# 07_power_input.net
KiCad netlist of a schematic drawn in Altium Designer
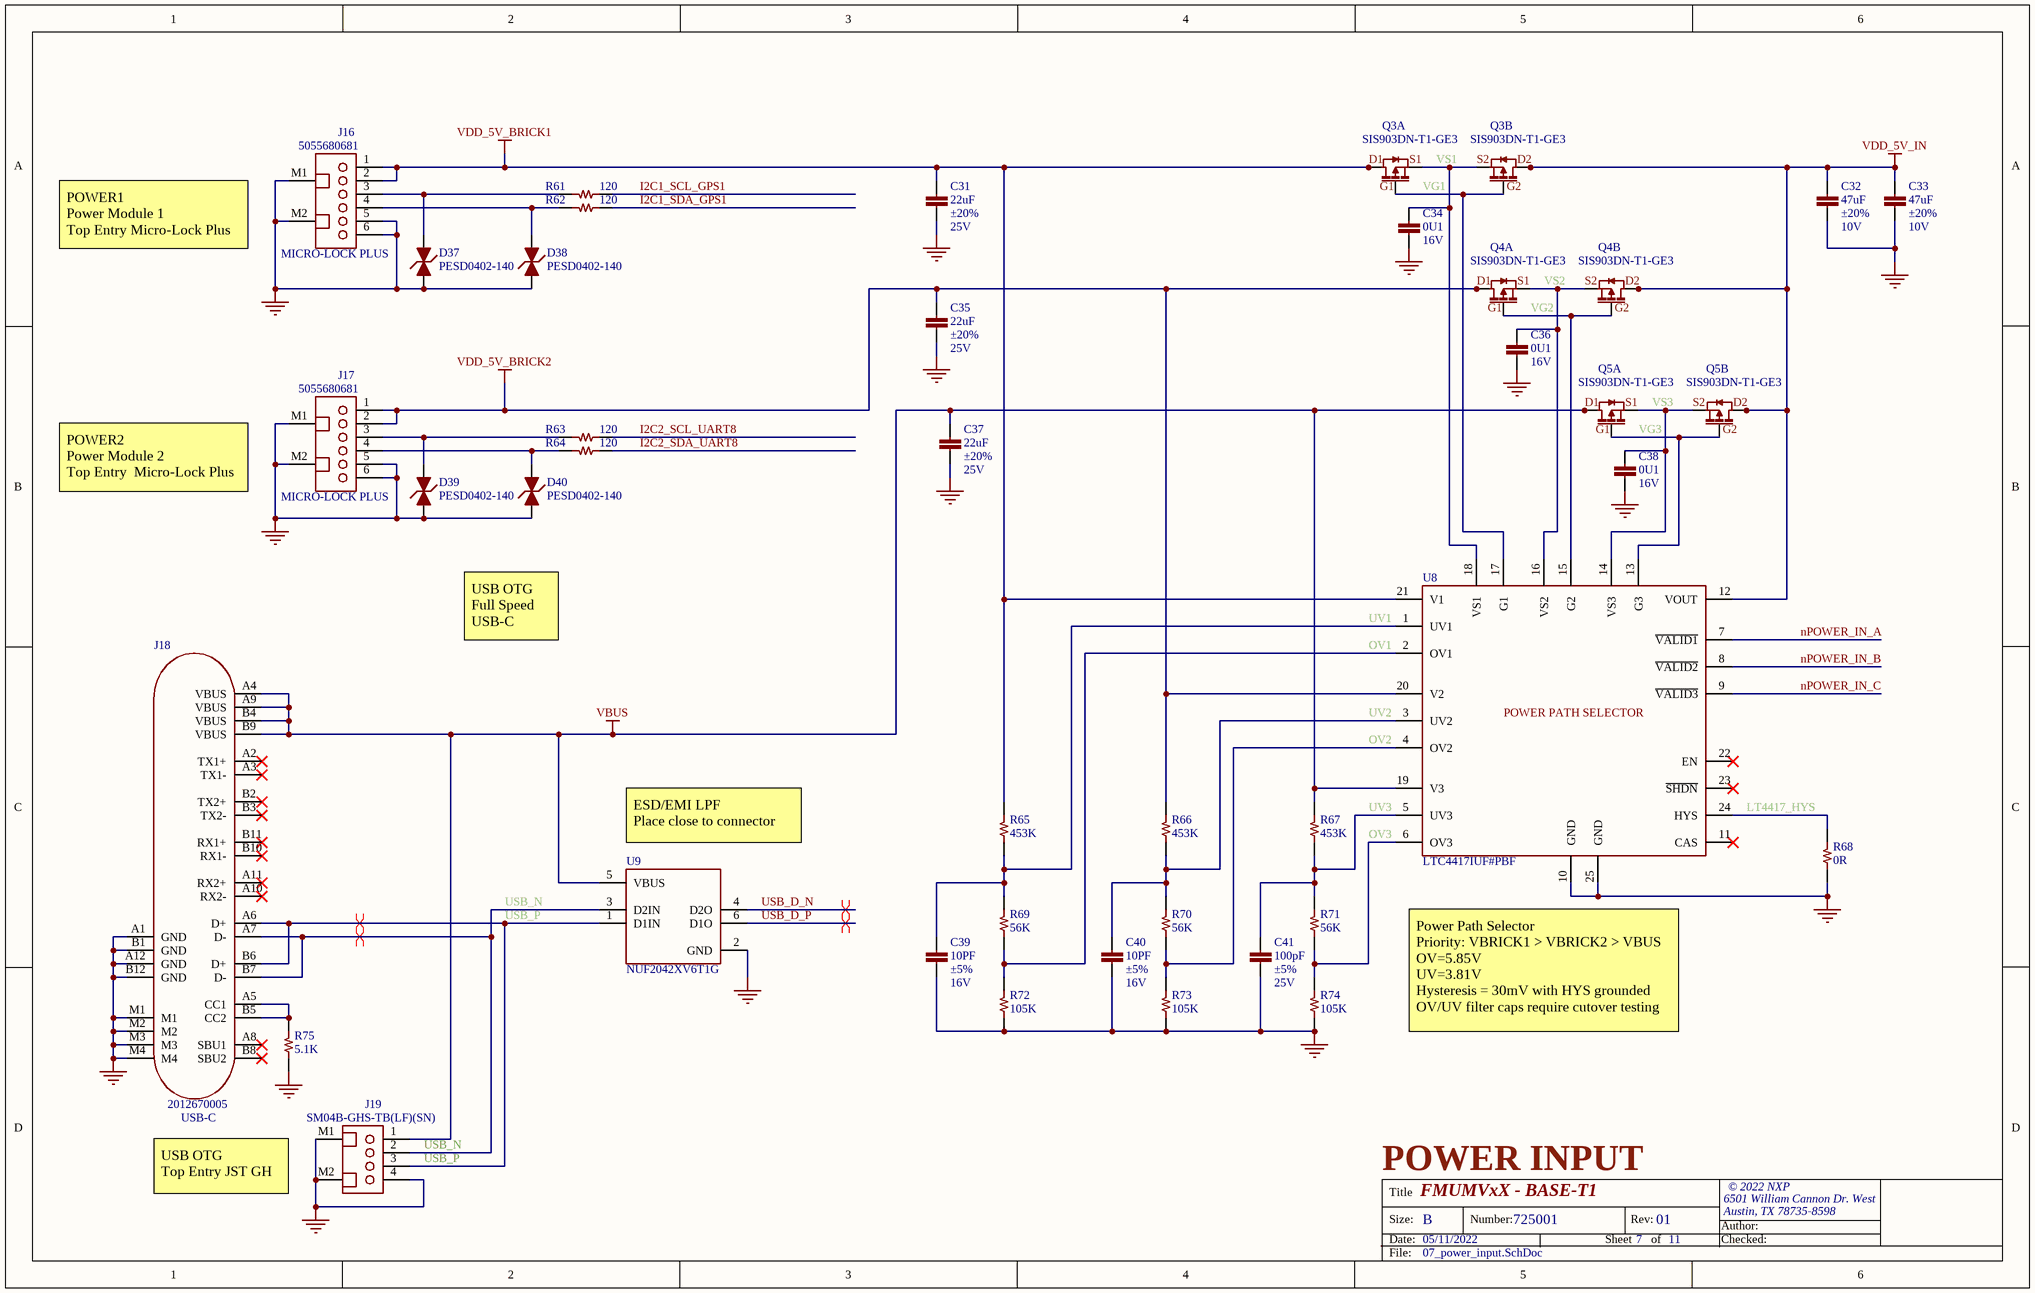
[diagram p0: 07_power_input.SchDoc]

(export (version "E")
  (design (tool "Eeschema 10.0.6"))
  (components
    (comp (ref "C31")
      (value "22uF")
      (footprint "CAPC200X125X70L40N")
      (description "CAP CER 22UF 20% 25V X5R 0805")
      (fields
        (field (name "MANUFACTURER") "Murata Electronics")
        (field (name "MANUFACTURER PART NUMBER") "GRT21BR61E226ME13L")
        (field (name "TOLERANCE") "±20%")
        (field (name "VOLTAGE - RATED") "25V")
      )
      (libsource (lib "NscDG_Integrated_Library") (part "CAP_22UF_20%_25V_X5R_0805"))
    )
    (comp (ref "C32")
      (value "47uF")
      (footprint "CAPC200X125X145L45N")
      (description "CAP CER 47UF 20% 10V X5R 0805")
      (fields
        (field (name "MANUFACTURER") "Murata Electronics North America")
        (field (name "MANUFACTURER PART NUMBER") "GRM21BR61A476ME15L")
        (field (name "TOLERANCE") "±20%")
        (field (name "VOLTAGE - RATED") "10V")
      )
      (libsource (lib "NscDG_Integrated_Library") (part "CAP_47UF_20%_10V_X5R_0805"))
    )
    (comp (ref "C33")
      (value "47uF")
      (footprint "CAPC200X125X145L45N")
      (description "CAP CER 47UF 20% 10V X5R 0805")
      (fields
        (field (name "MANUFACTURER") "Murata Electronics North America")
        (field (name "MANUFACTURER PART NUMBER") "GRM21BR61A476ME15L")
        (field (name "TOLERANCE") "±20%")
        (field (name "VOLTAGE - RATED") "10V")
      )
      (libsource (lib "NscDG_Integrated_Library") (part "CAP_47UF_20%_10V_X5R_0805"))
    )
    (comp (ref "C34")
      (value "0U1")
      (footprint "CAPC100X50X56L25N")
      (description "CAP CER 0.1UF 10% 16V X7R 0402")
      (fields
        (field (name "TOLERANCE") "±10%")
        (field (name "MANUFACTURER") "Murata Electronics")
        (field (name "VOLTAGE - RATED") "16V")
      )
      (libsource (lib "NscDG_Integrated_Library") (part "CAP_0U1_16V_X7R_0402"))
    )
    (comp (ref "C35")
      (value "22uF")
      (footprint "CAPC200X125X70L40N")
      (description "CAP CER 22UF 20% 25V X5R 0805")
      (fields
        (field (name "MANUFACTURER") "Murata Electronics")
        (field (name "MANUFACTURER PART NUMBER") "GRT21BR61E226ME13L")
        (field (name "TOLERANCE") "±20%")
        (field (name "VOLTAGE - RATED") "25V")
      )
      (libsource (lib "NscDG_Integrated_Library") (part "CAP_22UF_20%_25V_X5R_0805"))
    )
    (comp (ref "C36")
      (value "0U1")
      (footprint "CAPC100X50X56L25N")
      (description "CAP CER 0.1UF 10% 16V X7R 0402")
      (fields
        (field (name "TOLERANCE") "±10%")
        (field (name "MANUFACTURER") "Murata Electronics")
        (field (name "VOLTAGE - RATED") "16V")
      )
      (libsource (lib "NscDG_Integrated_Library") (part "CAP_0U1_16V_X7R_0402"))
    )
    (comp (ref "C37")
      (value "22uF")
      (footprint "CAPC200X125X70L40N")
      (description "CAP CER 22UF 20% 25V X5R 0805")
      (fields
        (field (name "MANUFACTURER") "Murata Electronics")
        (field (name "MANUFACTURER PART NUMBER") "GRT21BR61E226ME13L")
        (field (name "TOLERANCE") "±20%")
        (field (name "VOLTAGE - RATED") "25V")
      )
      (libsource (lib "NscDG_Integrated_Library") (part "CAP_22UF_20%_25V_X5R_0805"))
    )
    (comp (ref "C38")
      (value "0U1")
      (footprint "CAPC100X50X56L25N")
      (description "CAP CER 0.1UF 10% 16V X7R 0402")
      (fields
        (field (name "TOLERANCE") "±10%")
        (field (name "MANUFACTURER") "Murata Electronics")
        (field (name "VOLTAGE - RATED") "16V")
      )
      (libsource (lib "NscDG_Integrated_Library") (part "CAP_0U1_16V_X7R_0402"))
    )
    (comp (ref "C39")
      (value "10PF")
      (footprint "CAPC100X50X56L25N")
      (description "CAP CER 10PF 5% 16V C0G/NP0 0402")
      (fields
        (field (name "MANUFACTURER") "Wurth Electronics Inc.")
        (field (name "MANUFACTURER PART NUMBER") "885012005025")
        (field (name "TOLERANCE") "±5%")
        (field (name "VOLTAGE - RATED") "16V")
      )
      (libsource (lib "NscDG_Integrated_Library") (part "CAP_10PF_5%_16V_NPO_0402"))
    )
    (comp (ref "C40")
      (value "10PF")
      (footprint "CAPC100X50X56L25N")
      (description "CAP CER 10PF 5% 16V C0G/NP0 0402")
      (fields
        (field (name "MANUFACTURER") "Wurth Electronics Inc.")
        (field (name "MANUFACTURER PART NUMBER") "885012005025")
        (field (name "TOLERANCE") "±5%")
        (field (name "VOLTAGE - RATED") "16V")
      )
      (libsource (lib "NscDG_Integrated_Library") (part "CAP_10PF_5%_16V_NPO_0402"))
    )
    (comp (ref "C41")
      (value "100pF")
      (footprint "CAPC100X50X56L25N")
      (description "CAP CER 100PF 5% 25V COG/NPO 0402")
      (fields
        (field (name "MANUFACTURER") "KEMET")
        (field (name "MANUFACTURER PART NUMBER") "C0402C101J3GACTU")
        (field (name "TOLERANCE") "±5%")
        (field (name "VOLTAGE - RATED") "25V")
      )
      (libsource (lib "NscDG_Integrated_Library") (part "CAP_100PF_5%_25V_NPO_0402"))
    )
    (comp (ref "D37")
      (value "DIODE TVS BIDIRECTIONAL 14VWM 40VC 0402")
      (footprint "DIONC100X50X43L20N")
      (fields
        (field (name "MANUFACTURER") "Littelfuse Inc.")
        (field (name "MANUFACTURER PART NUMBER") "PESD0402-140")
      )
      (libsource (lib "NscDG_Integrated_Library") (part "DIODE_TVS_0402"))
    )
    (comp (ref "D38")
      (value "DIODE TVS BIDIRECTIONAL 14VWM 40VC 0402")
      (footprint "DIONC100X50X43L20N")
      (fields
        (field (name "MANUFACTURER") "Littelfuse Inc.")
        (field (name "MANUFACTURER PART NUMBER") "PESD0402-140")
      )
      (libsource (lib "NscDG_Integrated_Library") (part "DIODE_TVS_0402"))
    )
    (comp (ref "D39")
      (value "DIODE TVS BIDIRECTIONAL 14VWM 40VC 0402")
      (footprint "DIONC100X50X43L20N")
      (fields
        (field (name "MANUFACTURER") "Littelfuse Inc.")
        (field (name "MANUFACTURER PART NUMBER") "PESD0402-140")
      )
      (libsource (lib "NscDG_Integrated_Library") (part "DIODE_TVS_0402"))
    )
    (comp (ref "D40")
      (value "DIODE TVS BIDIRECTIONAL 14VWM 40VC 0402")
      (footprint "DIONC100X50X43L20N")
      (fields
        (field (name "MANUFACTURER") "Littelfuse Inc.")
        (field (name "MANUFACTURER PART NUMBER") "PESD0402-140")
      )
      (libsource (lib "NscDG_Integrated_Library") (part "DIODE_TVS_0402"))
    )
    (comp (ref "J16")
      (value "CONN HEADER MICRO-LOCK PLUS TOP 6POS 1.25MM SMT")
      (footprint "MOLEX_505568-0681")
      (fields
        (field (name "MANUFACTURER") "Molex, LLC")
        (field (name "ID") "MICRO-LOCK PLUS")
        (field (name "MANUFACTURER PART NUMBER") "5055680681")
      )
      (libsource (lib "NscDG_Integrated_Library") (part "CONN_HDR_1X6_RCPT_1.25MM_VERT_SMT"))
    )
    (comp (ref "J17")
      (value "CONN HEADER MICRO-LOCK PLUS TOP 6POS 1.25MM SMT")
      (footprint "MOLEX_505568-0681")
      (fields
        (field (name "MANUFACTURER") "Molex, LLC")
        (field (name "ID") "MICRO-LOCK PLUS")
        (field (name "MANUFACTURER PART NUMBER") "5055680681")
      )
      (libsource (lib "NscDG_Integrated_Library") (part "CONN_HDR_1X6_RCPT_1.25MM_VERT_SMT"))
    )
    (comp (ref "J18")
      (value "CONN RCPT USB C 3.1 SMT R/A SMD")
      (footprint "MOLEX_2012670005")
      (fields
        (field (name "MANUFACTURER") "Molex, LLC")
        (field (name "ID") "USB-C")
        (field (name "MANUFACTURER PART NUMBER") "2012670005")
      )
      (libsource (lib "NscDG_Integrated_Library") (part "CONN_RCPT_24POS_USB-C_RA-3_SMD"))
    )
    (comp (ref "J19")
      (value "CONN HEADER GH SIDE 4POS 1.25MM SMT")
      (footprint "JST_SM04B-GHS-TBLFSN")
      (fields
        (field (name "MANUFACTURER") "JST Sales America Inc.")
        (field (name "MANUFACTURER PART NUMBER") "SM04B-GHS-TB(LF)(SN)")
      )
      (libsource (lib "NscDG_Integrated_Library") (part "CONN_JST_GH_4PIN_RA_SMT"))
    )
    (comp (ref "Q3")
      (value "TRAN MOSFET 2P-CH 20V 6A PowerPAK")
      (footprint "VISHAY_POWERPAK_1212-8_DUAL")
      (fields
        (field (name "MANUFACTURER") "Vishay Siliconix")
        (field (name "MANUFACTURER PART NUMBER") "SIS903DN-T1-GE3")
      )
      (libsource (lib "NscDG_Integrated_Library") (part "TRAN_MOSFET_DUAL_PCHANNEL_PowerPAK"))
    )
    (comp (ref "Q4")
      (value "TRAN MOSFET 2P-CH 20V 6A PowerPAK")
      (footprint "VISHAY_POWERPAK_1212-8_DUAL")
      (fields
        (field (name "MANUFACTURER") "Vishay Siliconix")
        (field (name "MANUFACTURER PART NUMBER") "SIS903DN-T1-GE3")
      )
      (libsource (lib "NscDG_Integrated_Library") (part "TRAN_MOSFET_DUAL_PCHANNEL_PowerPAK"))
    )
    (comp (ref "Q5")
      (value "TRAN MOSFET 2P-CH 20V 6A PowerPAK")
      (footprint "VISHAY_POWERPAK_1212-8_DUAL")
      (fields
        (field (name "MANUFACTURER") "Vishay Siliconix")
        (field (name "MANUFACTURER PART NUMBER") "SIS903DN-T1-GE3")
      )
      (libsource (lib "NscDG_Integrated_Library") (part "TRAN_MOSFET_DUAL_PCHANNEL_PowerPAK"))
    )
    (comp (ref "R61")
      (value "120")
      (footprint "RESC100X50X40L25")
      (description "RES SMD 120 OHM 1% 1/16W 0402")
      (fields (field (name "TOLERANCE") "±1%") (field (name "MANUFACTURER") "Yageo"))
      (libsource (lib "NscDG_Integrated_Library") (part "RES_120_1%_1/16W_0402"))
    )
    (comp (ref "R62")
      (value "120")
      (footprint "RESC100X50X40L25")
      (description "RES SMD 120 OHM 1% 1/16W 0402")
      (fields (field (name "TOLERANCE") "±1%") (field (name "MANUFACTURER") "Yageo"))
      (libsource (lib "NscDG_Integrated_Library") (part "RES_120_1%_1/16W_0402"))
    )
    (comp (ref "R63")
      (value "120")
      (footprint "RESC100X50X40L25")
      (description "RES SMD 120 OHM 1% 1/16W 0402")
      (fields (field (name "TOLERANCE") "±1%") (field (name "MANUFACTURER") "Yageo"))
      (libsource (lib "NscDG_Integrated_Library") (part "RES_120_1%_1/16W_0402"))
    )
    (comp (ref "R64")
      (value "120")
      (footprint "RESC100X50X40L25")
      (description "RES SMD 120 OHM 1% 1/16W 0402")
      (fields (field (name "TOLERANCE") "±1%") (field (name "MANUFACTURER") "Yageo"))
      (libsource (lib "NscDG_Integrated_Library") (part "RES_120_1%_1/16W_0402"))
    )
    (comp (ref "R65")
      (value "453K")
      (footprint "RESC100X50X40L25")
      (description "RES SMD 453K OHM 1% 1/16W 0402")
      (fields (field (name "TOLERANCE") "±1%") (field (name "MANUFACTURER") "Yageo"))
      (libsource (lib "NscDG_Integrated_Library") (part "RES_453K_1%_1/16W_0402"))
    )
    (comp (ref "R66")
      (value "453K")
      (footprint "RESC100X50X40L25")
      (description "RES SMD 453K OHM 1% 1/16W 0402")
      (fields (field (name "TOLERANCE") "±1%") (field (name "MANUFACTURER") "Yageo"))
      (libsource (lib "NscDG_Integrated_Library") (part "RES_453K_1%_1/16W_0402"))
    )
    (comp (ref "R67")
      (value "453K")
      (footprint "RESC100X50X40L25")
      (description "RES SMD 453K OHM 1% 1/16W 0402")
      (fields (field (name "TOLERANCE") "±1%") (field (name "MANUFACTURER") "Yageo"))
      (libsource (lib "NscDG_Integrated_Library") (part "RES_453K_1%_1/16W_0402"))
    )
    (comp (ref "R68")
      (value "0R")
      (footprint "RESC100X50X40L25")
      (description "RES SMD 0 OHM 1% 1/16W 0402")
      (fields (field (name "TOLERANCE") "±1%") (field (name "MANUFACTURER") "Yageo"))
      (libsource (lib "NscDG_Integrated_Library") (part "RES_0R_1%_1/16W_0402"))
    )
    (comp (ref "R69")
      (value "56K")
      (footprint "RESC100X50X40L25")
      (description "RES SMD 56K OHM 1% 1/16W 0402")
      (fields (field (name "TOLERANCE") "±1%") (field (name "MANUFACTURER") "Yageo"))
      (libsource (lib "NscDG_Integrated_Library") (part "RES_56K_1%_1/16W_0402"))
    )
    (comp (ref "R70")
      (value "56K")
      (footprint "RESC100X50X40L25")
      (description "RES SMD 56K OHM 1% 1/16W 0402")
      (fields (field (name "TOLERANCE") "±1%") (field (name "MANUFACTURER") "Yageo"))
      (libsource (lib "NscDG_Integrated_Library") (part "RES_56K_1%_1/16W_0402"))
    )
    (comp (ref "R71")
      (value "56K")
      (footprint "RESC100X50X40L25")
      (description "RES SMD 56K OHM 1% 1/16W 0402")
      (fields (field (name "TOLERANCE") "±1%") (field (name "MANUFACTURER") "Yageo"))
      (libsource (lib "NscDG_Integrated_Library") (part "RES_56K_1%_1/16W_0402"))
    )
    (comp (ref "R72")
      (value "105K")
      (footprint "RESC100X50X40L25")
      (description "RES SMD 105K OHM 1% 1/16W 0402")
      (fields (field (name "TOLERANCE") "±1%") (field (name "MANUFACTURER") "Yageo"))
      (libsource (lib "NscDG_Integrated_Library") (part "RES_105K_1%_1/16W_0402"))
    )
    (comp (ref "R73")
      (value "105K")
      (footprint "RESC100X50X40L25")
      (description "RES SMD 105K OHM 1% 1/16W 0402")
      (fields (field (name "TOLERANCE") "±1%") (field (name "MANUFACTURER") "Yageo"))
      (libsource (lib "NscDG_Integrated_Library") (part "RES_105K_1%_1/16W_0402"))
    )
    (comp (ref "R74")
      (value "105K")
      (footprint "RESC100X50X40L25")
      (description "RES SMD 105K OHM 1% 1/16W 0402")
      (fields (field (name "TOLERANCE") "±1%") (field (name "MANUFACTURER") "Yageo"))
      (libsource (lib "NscDG_Integrated_Library") (part "RES_105K_1%_1/16W_0402"))
    )
    (comp (ref "R75")
      (value "5.1K")
      (footprint "RESC100X50X40L25")
      (description "RES SMD 5.1K OHM 1% 1/16W 0402")
      (fields (field (name "TOLERANCE") "±1%") (field (name "MANUFACTURER") "Yageo"))
      (libsource (lib "NscDG_Integrated_Library") (part "RES_5.1K_1%_1/16W_0402"))
    )
    (comp (ref "U8")
      (value "IC OR CTRLR SRC SELECT 24QFN")
      (footprint "QFN25P50_400X400X80L40X25T245N")
      (fields
        (field (name "MANUFACTURER") "Linear Technology/Analog Devices")
        (field (name "MANUFACTURER PART NUMBER") "LTC4417IUF#PBF")
      )
      (libsource (lib "NscDG_Integrated_Library") (part "IC_LTC4417"))
    )
    (comp (ref "U9")
      (value "IC FILTER RC(PI) 22 OHM/42PF SOT-563")
      (footprint "SOFL6P50_160X160X60L20X22")
      (fields
        (field (name "MANUFACTURER") "ON Semiconductor")
        (field (name "MANUFACTURER PART NUMBER") "NUF2042XV6T1G")
      )
      (libsource (lib "NscDG_Integrated_Library") (part "IC_NUF2042XV6_SOT563"))
    )
  )
  (nets
    (net (code "1") (name "/I2C1_SCL_GPS1") (class "Default")
      (node (ref "R61") (pin "2") (pinfunction "2_2") (pintype "passive"))
    )
    (net (code "2") (name "/I2C1_SDA_GPS1") (class "Default")
      (node (ref "R62") (pin "2") (pinfunction "2_2") (pintype "passive"))
    )
    (net (code "3") (name "/I2C2_SCL_UART8") (class "Default")
      (node (ref "R63") (pin "2") (pinfunction "2_2") (pintype "passive"))
    )
    (net (code "4") (name "/I2C2_SDA_UART8") (class "Default")
      (node (ref "R64") (pin "2") (pinfunction "2_2") (pintype "passive"))
    )
    (net (code "5") (name "/LT4417_HYS") (class "Default")
      (node (ref "R68") (pin "1") (pinfunction "1_1") (pintype "passive"))
      (node (ref "U8") (pin "24") (pinfunction "HYS_24") (pintype "passive"))
    )
    (net (code "6") (name "/OV1") (class "Default")
      (node (ref "R69") (pin "2") (pinfunction "2_2") (pintype "passive"))
      (node (ref "R72") (pin "1") (pinfunction "1_1") (pintype "passive"))
      (node (ref "U8") (pin "2") (pinfunction "OV1_2") (pintype "passive"))
    )
    (net (code "7") (name "/OV2") (class "Default")
      (node (ref "R70") (pin "2") (pinfunction "2_2") (pintype "passive"))
      (node (ref "R73") (pin "1") (pinfunction "1_1") (pintype "passive"))
      (node (ref "U8") (pin "4") (pinfunction "OV2_4") (pintype "passive"))
    )
    (net (code "8") (name "/OV3") (class "Default")
      (node (ref "R71") (pin "2") (pinfunction "2_2") (pintype "passive"))
      (node (ref "R74") (pin "1") (pinfunction "1_1") (pintype "passive"))
      (node (ref "U8") (pin "6") (pinfunction "OV3_6") (pintype "passive"))
    )
    (net (code "9") (name "/USB_D_N") (class "Default")
      (node (ref "U9") (pin "4") (pinfunction "D2O_4") (pintype "passive"))
    )
    (net (code "10") (name "/USB_D_P") (class "Default")
      (node (ref "U9") (pin "6") (pinfunction "D1O_6") (pintype "passive"))
    )
    (net (code "11") (name "/USB_N") (class "Default")
      (node (ref "J18") (pin "A7") (pinfunction "D-_A7") (pintype "passive"))
      (node (ref "J18") (pin "B7") (pinfunction "D-_B7") (pintype "passive"))
      (node (ref "J19") (pin "2") (pinfunction "2_2") (pintype "passive"))
      (node (ref "U9") (pin "3") (pinfunction "D2IN_3") (pintype "passive"))
    )
    (net (code "12") (name "/USB_P") (class "Default")
      (node (ref "J18") (pin "A6") (pinfunction "D+_A6") (pintype "passive"))
      (node (ref "J18") (pin "B6") (pinfunction "D+_B6") (pintype "passive"))
      (node (ref "J19") (pin "3") (pinfunction "3_3") (pintype "passive"))
      (node (ref "U9") (pin "1") (pinfunction "D1IN_1") (pintype "passive"))
    )
    (net (code "13") (name "/UV1") (class "Default")
      (node (ref "C39") (pin "1") (pinfunction "1_1") (pintype "passive"))
      (node (ref "R65") (pin "2") (pinfunction "2_2") (pintype "passive"))
      (node (ref "R69") (pin "1") (pinfunction "1_1") (pintype "passive"))
      (node (ref "U8") (pin "1") (pinfunction "UV1_1") (pintype "passive"))
    )
    (net (code "14") (name "/UV2") (class "Default")
      (node (ref "C40") (pin "1") (pinfunction "1_1") (pintype "passive"))
      (node (ref "R66") (pin "2") (pinfunction "2_2") (pintype "passive"))
      (node (ref "R70") (pin "1") (pinfunction "1_1") (pintype "passive"))
      (node (ref "U8") (pin "3") (pinfunction "UV2_3") (pintype "passive"))
    )
    (net (code "15") (name "/UV3") (class "Default")
      (node (ref "C41") (pin "1") (pinfunction "1_1") (pintype "passive"))
      (node (ref "R67") (pin "2") (pinfunction "2_2") (pintype "passive"))
      (node (ref "R71") (pin "1") (pinfunction "1_1") (pintype "passive"))
      (node (ref "U8") (pin "5") (pinfunction "UV3_5") (pintype "passive"))
    )
    (net (code "16") (name "/VG1") (class "Default")
      (node (ref "Q3") (pin "2") (pinfunction "G1_2") (pintype "passive"))
      (node (ref "Q3") (pin "4") (pinfunction "G2_4") (pintype "passive"))
      (node (ref "U8") (pin "17") (pinfunction "G1_17") (pintype "passive"))
    )
    (net (code "17") (name "/VG2") (class "Default")
      (node (ref "Q4") (pin "2") (pinfunction "G1_2") (pintype "passive"))
      (node (ref "Q4") (pin "4") (pinfunction "G2_4") (pintype "passive"))
      (node (ref "U8") (pin "15") (pinfunction "G2_15") (pintype "passive"))
    )
    (net (code "18") (name "/VG3") (class "Default")
      (node (ref "Q5") (pin "2") (pinfunction "G1_2") (pintype "passive"))
      (node (ref "Q5") (pin "4") (pinfunction "G2_4") (pintype "passive"))
      (node (ref "U8") (pin "13") (pinfunction "G3_13") (pintype "passive"))
    )
    (net (code "19") (name "/VS1") (class "Default")
      (node (ref "C34") (pin "1") (pinfunction "1_1") (pintype "passive"))
      (node (ref "Q3") (pin "1") (pinfunction "S1_1") (pintype "passive"))
      (node (ref "Q3") (pin "3") (pinfunction "S2_3") (pintype "passive"))
      (node (ref "U8") (pin "18") (pinfunction "VS1_18") (pintype "passive"))
    )
    (net (code "20") (name "/VS2") (class "Default")
      (node (ref "C36") (pin "1") (pinfunction "1_1") (pintype "passive"))
      (node (ref "Q4") (pin "1") (pinfunction "S1_1") (pintype "passive"))
      (node (ref "Q4") (pin "3") (pinfunction "S2_3") (pintype "passive"))
      (node (ref "U8") (pin "16") (pinfunction "VS2_16") (pintype "passive"))
    )
    (net (code "21") (name "/VS3") (class "Default")
      (node (ref "C38") (pin "1") (pinfunction "1_1") (pintype "passive"))
      (node (ref "Q5") (pin "1") (pinfunction "S1_1") (pintype "passive"))
      (node (ref "Q5") (pin "3") (pinfunction "S2_3") (pintype "passive"))
      (node (ref "U8") (pin "14") (pinfunction "VS3_14") (pintype "passive"))
    )
    (net (code "22") (name "/nPOWER_IN_A") (class "Default")
      (node (ref "U8") (pin "7") (pinfunction "~{VALID1}_7") (pintype "passive"))
    )
    (net (code "23") (name "/nPOWER_IN_B") (class "Default")
      (node (ref "U8") (pin "8") (pinfunction "~{VALID2}_8") (pintype "passive"))
    )
    (net (code "24") (name "/nPOWER_IN_C") (class "Default")
      (node (ref "U8") (pin "9") (pinfunction "~{VALID3}_9") (pintype "passive"))
    )
    (net (code "25") (name "GND") (class "Default")
      (node (ref "C31") (pin "2") (pinfunction "2_2") (pintype "passive"))
      (node (ref "C32") (pin "2") (pinfunction "2_2") (pintype "passive"))
      (node (ref "C33") (pin "2") (pinfunction "2_2") (pintype "passive"))
      (node (ref "C34") (pin "2") (pinfunction "2_2") (pintype "passive"))
      (node (ref "C35") (pin "2") (pinfunction "2_2") (pintype "passive"))
      (node (ref "C36") (pin "2") (pinfunction "2_2") (pintype "passive"))
      (node (ref "C37") (pin "2") (pinfunction "2_2") (pintype "passive"))
      (node (ref "C38") (pin "2") (pinfunction "2_2") (pintype "passive"))
      (node (ref "C39") (pin "2") (pinfunction "2_2") (pintype "passive"))
      (node (ref "C40") (pin "2") (pinfunction "2_2") (pintype "passive"))
      (node (ref "C41") (pin "2") (pinfunction "2_2") (pintype "passive"))
      (node (ref "D37") (pin "1") (pinfunction "1_1") (pintype "passive"))
      (node (ref "D38") (pin "1") (pinfunction "1_1") (pintype "passive"))
      (node (ref "D39") (pin "1") (pinfunction "1_1") (pintype "passive"))
      (node (ref "D40") (pin "1") (pinfunction "1_1") (pintype "passive"))
      (node (ref "J16") (pin "5") (pinfunction "5_5") (pintype "passive"))
      (node (ref "J16") (pin "6") (pinfunction "6_6") (pintype "passive"))
      (node (ref "J16") (pin "M1") (pinfunction "M1_M1") (pintype "passive"))
      (node (ref "J16") (pin "M2") (pinfunction "M2_M2") (pintype "passive"))
      (node (ref "J17") (pin "5") (pinfunction "5_5") (pintype "passive"))
      (node (ref "J17") (pin "6") (pinfunction "6_6") (pintype "passive"))
      (node (ref "J17") (pin "M1") (pinfunction "M1_M1") (pintype "passive"))
      (node (ref "J17") (pin "M2") (pinfunction "M2_M2") (pintype "passive"))
      (node (ref "J18") (pin "A1") (pinfunction "GND_A1") (pintype "passive"))
      (node (ref "J18") (pin "A12") (pinfunction "GND_A12") (pintype "passive"))
      (node (ref "J18") (pin "B1") (pinfunction "GND_B1") (pintype "passive"))
      (node (ref "J18") (pin "B12") (pinfunction "GND_B12") (pintype "passive"))
      (node (ref "J18") (pin "M1") (pinfunction "M1_M1") (pintype "passive"))
      (node (ref "J18") (pin "M2") (pinfunction "M2_M2") (pintype "passive"))
      (node (ref "J18") (pin "M3") (pinfunction "M3_M3") (pintype "passive"))
      (node (ref "J18") (pin "M4") (pinfunction "M4_M4") (pintype "passive"))
      (node (ref "J19") (pin "4") (pinfunction "4_4") (pintype "passive"))
      (node (ref "J19") (pin "M1") (pinfunction "M1_M1") (pintype "passive"))
      (node (ref "J19") (pin "M2") (pinfunction "M2_M2") (pintype "passive"))
      (node (ref "R68") (pin "2") (pinfunction "2_2") (pintype "passive"))
      (node (ref "R72") (pin "2") (pinfunction "2_2") (pintype "passive"))
      (node (ref "R73") (pin "2") (pinfunction "2_2") (pintype "passive"))
      (node (ref "R74") (pin "2") (pinfunction "2_2") (pintype "passive"))
      (node (ref "R75") (pin "2") (pinfunction "2_2") (pintype "passive"))
      (node (ref "U8") (pin "10") (pinfunction "GND_10") (pintype "passive"))
      (node (ref "U8") (pin "25") (pinfunction "GND_25") (pintype "passive"))
      (node (ref "U9") (pin "2") (pinfunction "GND_2") (pintype "passive"))
    )
    (net (code "26") (name "Net-(D37-Pad2)") (class "Default")
      (node (ref "D37") (pin "2") (pinfunction "2_2") (pintype "passive"))
      (node (ref "J16") (pin "3") (pinfunction "3_3") (pintype "passive"))
      (node (ref "R61") (pin "1") (pinfunction "1_1") (pintype "passive"))
    )
    (net (code "27") (name "Net-(D38-Pad2)") (class "Default")
      (node (ref "D38") (pin "2") (pinfunction "2_2") (pintype "passive"))
      (node (ref "J16") (pin "4") (pinfunction "4_4") (pintype "passive"))
      (node (ref "R62") (pin "1") (pinfunction "1_1") (pintype "passive"))
    )
    (net (code "28") (name "Net-(D39-Pad2)") (class "Default")
      (node (ref "D39") (pin "2") (pinfunction "2_2") (pintype "passive"))
      (node (ref "J17") (pin "3") (pinfunction "3_3") (pintype "passive"))
      (node (ref "R63") (pin "1") (pinfunction "1_1") (pintype "passive"))
    )
    (net (code "29") (name "Net-(D40-Pad2)") (class "Default")
      (node (ref "D40") (pin "2") (pinfunction "2_2") (pintype "passive"))
      (node (ref "J17") (pin "4") (pinfunction "4_4") (pintype "passive"))
      (node (ref "R64") (pin "1") (pinfunction "1_1") (pintype "passive"))
    )
    (net (code "30") (name "Net-(J18-CC1)") (class "Default")
      (node (ref "J18") (pin "A5") (pinfunction "CC1_A5") (pintype "passive"))
      (node (ref "J18") (pin "B5") (pinfunction "CC2_B5") (pintype "passive"))
      (node (ref "R75") (pin "1") (pinfunction "1_1") (pintype "passive"))
    )
    (net (code "31") (name "VBUS") (class "Default")
      (node (ref "C37") (pin "1") (pinfunction "1_1") (pintype "passive"))
      (node (ref "J18") (pin "A4") (pinfunction "VBUS_A4") (pintype "power_in"))
      (node (ref "J18") (pin "A9") (pinfunction "VBUS_A9") (pintype "power_in"))
      (node (ref "J18") (pin "B4") (pinfunction "VBUS_B4") (pintype "power_in"))
      (node (ref "J18") (pin "B9") (pinfunction "VBUS_B9") (pintype "power_in"))
      (node (ref "J19") (pin "1") (pinfunction "1_1") (pintype "passive"))
      (node (ref "Q5") (pin "7") (pinfunction "D1_7") (pintype "passive"))
      (node (ref "Q5") (pin "8") (pinfunction "D1_8") (pintype "passive"))
      (node (ref "R67") (pin "1") (pinfunction "1_1") (pintype "passive"))
      (node (ref "U8") (pin "19") (pinfunction "V3_19") (pintype "passive"))
      (node (ref "U9") (pin "5") (pinfunction "VBUS_5") (pintype "power_in"))
    )
    (net (code "32") (name "VDD_5V_BRICK1") (class "Default")
      (node (ref "C31") (pin "1") (pinfunction "1_1") (pintype "passive"))
      (node (ref "J16") (pin "1") (pinfunction "1_1") (pintype "passive"))
      (node (ref "J16") (pin "2") (pinfunction "2_2") (pintype "passive"))
      (node (ref "Q3") (pin "7") (pinfunction "D1_7") (pintype "passive"))
      (node (ref "Q3") (pin "8") (pinfunction "D1_8") (pintype "passive"))
      (node (ref "R65") (pin "1") (pinfunction "1_1") (pintype "passive"))
      (node (ref "U8") (pin "21") (pinfunction "V1_21") (pintype "passive"))
    )
    (net (code "33") (name "VDD_5V_BRICK2") (class "Default")
      (node (ref "C35") (pin "1") (pinfunction "1_1") (pintype "passive"))
      (node (ref "J17") (pin "1") (pinfunction "1_1") (pintype "passive"))
      (node (ref "J17") (pin "2") (pinfunction "2_2") (pintype "passive"))
      (node (ref "Q4") (pin "7") (pinfunction "D1_7") (pintype "passive"))
      (node (ref "Q4") (pin "8") (pinfunction "D1_8") (pintype "passive"))
      (node (ref "R66") (pin "1") (pinfunction "1_1") (pintype "passive"))
      (node (ref "U8") (pin "20") (pinfunction "V2_20") (pintype "passive"))
    )
    (net (code "34") (name "VDD_5V_IN") (class "Default")
      (node (ref "C32") (pin "1") (pinfunction "1_1") (pintype "passive"))
      (node (ref "C33") (pin "1") (pinfunction "1_1") (pintype "passive"))
      (node (ref "Q3") (pin "5") (pinfunction "D2_5") (pintype "passive"))
      (node (ref "Q3") (pin "6") (pinfunction "D2_6") (pintype "passive"))
      (node (ref "Q4") (pin "5") (pinfunction "D2_5") (pintype "passive"))
      (node (ref "Q4") (pin "6") (pinfunction "D2_6") (pintype "passive"))
      (node (ref "Q5") (pin "5") (pinfunction "D2_5") (pintype "passive"))
      (node (ref "Q5") (pin "6") (pinfunction "D2_6") (pintype "passive"))
      (node (ref "U8") (pin "12") (pinfunction "VOUT_12") (pintype "passive"))
    )
    (net (code "35") (name "unconnected-(J18-RX1+-PadB11)") (class "Default")
      (node (ref "J18") (pin "B11") (pinfunction "RX1+_B11") (pintype "passive+no_connect"))
    )
    (net (code "36") (name "unconnected-(J18-RX1--PadB10)") (class "Default")
      (node (ref "J18") (pin "B10") (pinfunction "RX1-_B10") (pintype "passive+no_connect"))
    )
    (net (code "37") (name "unconnected-(J18-RX2+-PadA11)") (class "Default")
      (node (ref "J18") (pin "A11") (pinfunction "RX2+_A11") (pintype "passive+no_connect"))
    )
    (net (code "38") (name "unconnected-(J18-RX2--PadA10)") (class "Default")
      (node (ref "J18") (pin "A10") (pinfunction "RX2-_A10") (pintype "passive+no_connect"))
    )
    (net (code "39") (name "unconnected-(J18-SBU1-PadA8)") (class "Default")
      (node (ref "J18") (pin "A8") (pinfunction "SBU1_A8") (pintype "passive+no_connect"))
    )
    (net (code "40") (name "unconnected-(J18-SBU2-PadB8)") (class "Default")
      (node (ref "J18") (pin "B8") (pinfunction "SBU2_B8") (pintype "passive+no_connect"))
    )
    (net (code "41") (name "unconnected-(J18-TX1+-PadA2)") (class "Default")
      (node (ref "J18") (pin "A2") (pinfunction "TX1+_A2") (pintype "passive+no_connect"))
    )
    (net (code "42") (name "unconnected-(J18-TX1--PadA3)") (class "Default")
      (node (ref "J18") (pin "A3") (pinfunction "TX1-_A3") (pintype "passive+no_connect"))
    )
    (net (code "43") (name "unconnected-(J18-TX2+-PadB2)") (class "Default")
      (node (ref "J18") (pin "B2") (pinfunction "TX2+_B2") (pintype "passive+no_connect"))
    )
    (net (code "44") (name "unconnected-(J18-TX2--PadB3)") (class "Default")
      (node (ref "J18") (pin "B3") (pinfunction "TX2-_B3") (pintype "passive+no_connect"))
    )
    (net (code "45") (name "unconnected-(U8-CAS-Pad11)") (class "Default")
      (node (ref "U8") (pin "11") (pinfunction "CAS_11") (pintype "passive+no_connect"))
    )
    (net (code "46") (name "unconnected-(U8-EN-Pad22)") (class "Default")
      (node (ref "U8") (pin "22") (pinfunction "EN_22") (pintype "passive+no_connect"))
    )
    (net (code "47") (name "unconnected-(U8-~{SHDN}-Pad23)") (class "Default")
      (node (ref "U8") (pin "23") (pinfunction "~{SHDN}_23") (pintype "passive+no_connect"))
    )
  )
)
